# H_Connecties.net
KiCad netlist of a schematic drawn in Altium Designer
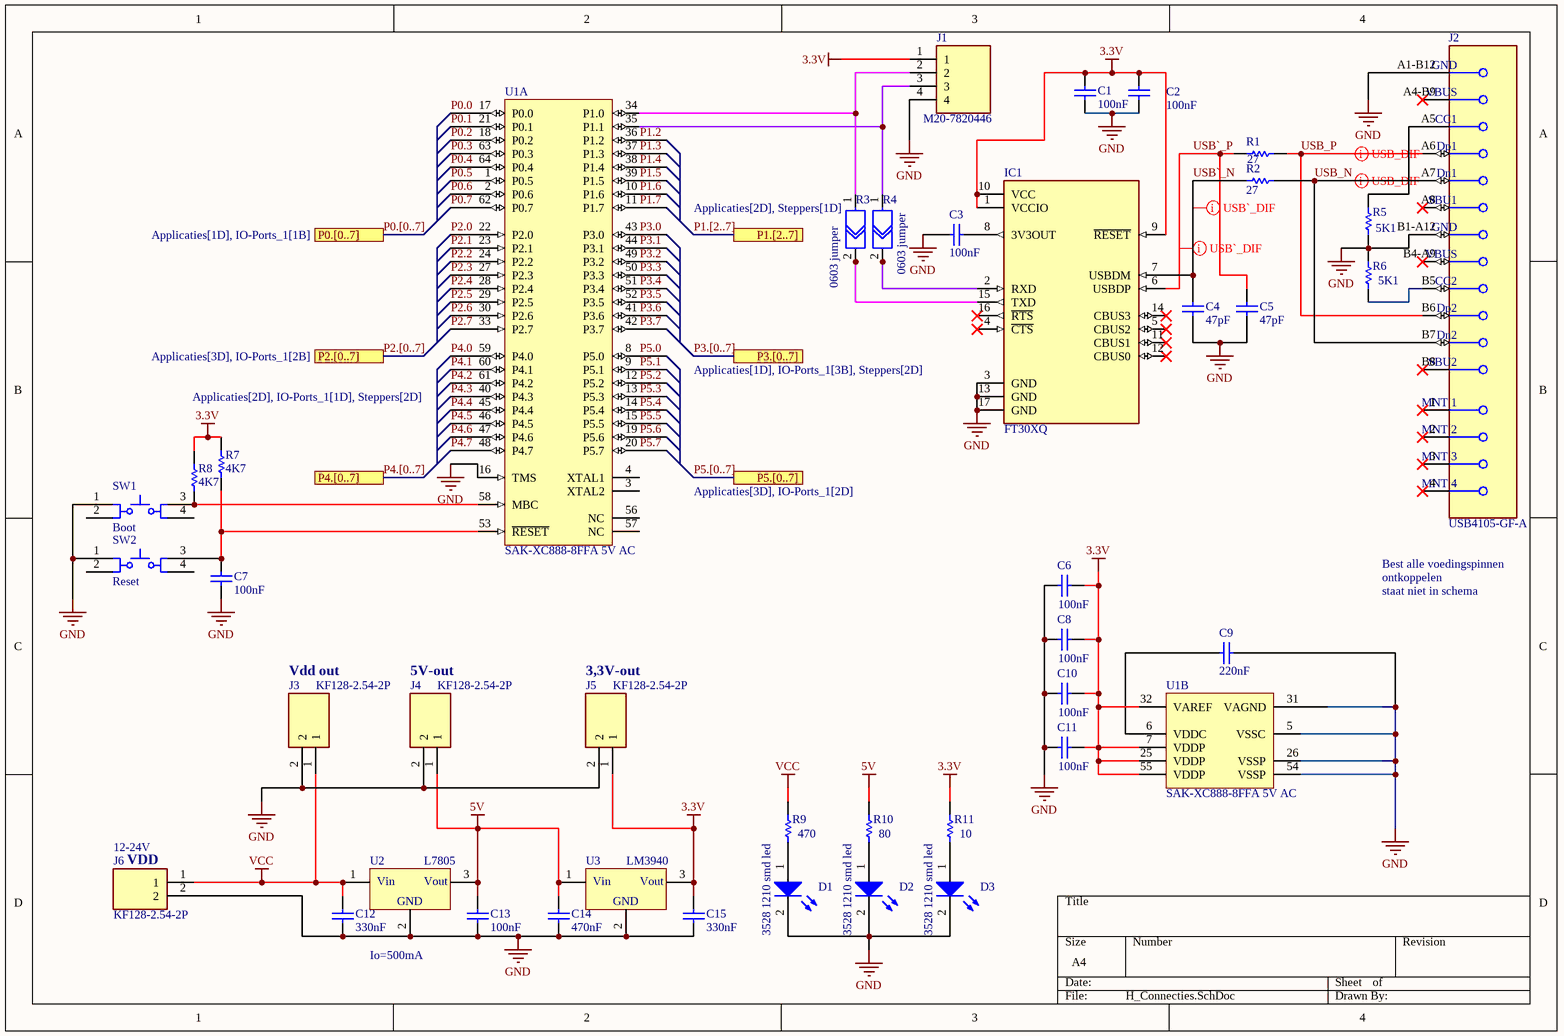
[diagram p0: H_Connecties.SchDoc]

(export (version "E")
  (design (tool "Eeschema 10.0.6"))
  (components
    (comp (ref "C1")
      (value "100nF")
      (footprint "CAPC1608X90X35LL15T15")
      (fields
        (field (name "MANUFACTURER") "AVX Interconnect / Elco")
        (field (name "PART NUMBER") "0603ZC101KAT2A")
      )
      (libsource (lib "Altium Content Vault") (part "CAP"))
    )
    (comp (ref "C2")
      (value "100nF")
      (footprint "CAPC1608X90X35LL15T15")
      (fields
        (field (name "MANUFACTURER") "AVX Interconnect / Elco")
        (field (name "PART NUMBER") "0603ZC101KAT2A")
      )
      (libsource (lib "Altium Content Vault") (part "CAP"))
    )
    (comp (ref "C3")
      (value "100nF")
      (footprint "CAPC1608X90X35LL15T15")
      (fields
        (field (name "MANUFACTURER") "AVX Interconnect / Elco")
        (field (name "PART NUMBER") "0603ZC101KAT2A")
      )
      (libsource (lib "Altium Content Vault") (part "CAP"))
    )
    (comp (ref "C4")
      (value "47pF")
      (footprint "CAPC1608X90X35LL15T15")
      (fields
        (field (name "MANUFACTURER") "AVX Interconnect / Elco")
        (field (name "PART NUMBER") "0603ZC101KAT2A")
      )
      (libsource (lib "Altium Content Vault") (part "CAP"))
    )
    (comp (ref "C5")
      (value "47pF")
      (footprint "CAPC1608X90X35LL15T15")
      (fields
        (field (name "MANUFACTURER") "AVX Interconnect / Elco")
        (field (name "PART NUMBER") "0603ZC101KAT2A")
      )
      (libsource (lib "Altium Content Vault") (part "CAP"))
    )
    (comp (ref "C6")
      (value "100nF")
      (footprint "CAPC1608X92X38NL15T08")
      (fields (field (name "MANUFACTURER") "Vitramon") (field (name "PART NUMBER") "VJ0603Y104KXJAP"))
      (libsource (lib "Altium Content Vault") (part "CAP"))
    )
    (comp (ref "C7")
      (value "100nF")
      (footprint "CAPC1608X90X35LL15T15")
      (fields
        (field (name "MANUFACTURER") "AVX Interconnect / Elco")
        (field (name "PART NUMBER") "0603ZC101KAT2A")
      )
      (libsource (lib "Altium Content Vault") (part "CAP"))
    )
    (comp (ref "C8")
      (value "100nF")
      (footprint "CAPC1608X92X38NL15T08")
      (fields (field (name "MANUFACTURER") "Vitramon") (field (name "PART NUMBER") "VJ0603Y104KXJAP"))
      (libsource (lib "Altium Content Vault") (part "CAP"))
    )
    (comp (ref "C9")
      (value "220nF")
      (footprint "CAPC1608X95X40LL15T15")
      (fields (field (name "PART NUMBER") "VJ0603Y224KXXCW1BC") (field (name "MANUFACTURER") "Vitramon"))
      (libsource (lib "Altium Content Vault") (part "CAP"))
    )
    (comp (ref "C10")
      (value "100nF")
      (footprint "CAPC1608X92X38NL15T08")
      (fields (field (name "MANUFACTURER") "Vitramon") (field (name "PART NUMBER") "VJ0603Y104KXJAP"))
      (libsource (lib "Altium Content Vault") (part "CAP"))
    )
    (comp (ref "C11")
      (value "100nF")
      (footprint "CAPC1608X92X38NL15T08")
      (fields (field (name "MANUFACTURER") "Vitramon") (field (name "PART NUMBER") "VJ0603Y104KXJAP"))
      (libsource (lib "Altium Content Vault") (part "CAP"))
    )
    (comp (ref "C12")
      (value "330nF")
      (footprint "CAPC1608X90X35LL15T15")
      (fields
        (field (name "MANUFACTURER") "AVX Interconnect / Elco")
        (field (name "PART NUMBER") "0603ZC101KAT2A")
      )
      (libsource (lib "Altium Content Vault") (part "CAP"))
    )
    (comp (ref "C13")
      (value "100nF")
      (footprint "CAPC1608X90X35LL15T15")
      (fields
        (field (name "MANUFACTURER") "AVX Interconnect / Elco")
        (field (name "PART NUMBER") "0603ZC101KAT2A")
      )
      (libsource (lib "Altium Content Vault") (part "CAP"))
    )
    (comp (ref "C14")
      (value "470nF")
      (footprint "CAPC1608X90X35LL15T15")
      (fields
        (field (name "MANUFACTURER") "AVX Interconnect / Elco")
        (field (name "PART NUMBER") "0603ZC101KAT2A")
      )
      (libsource (lib "Altium Content Vault") (part "CAP"))
    )
    (comp (ref "C15")
      (value "330nF")
      (footprint "CAPC1608X90X35LL15T15")
      (fields
        (field (name "MANUFACTURER") "AVX Interconnect / Elco")
        (field (name "PART NUMBER") "0603ZC101KAT2A")
      )
      (libsource (lib "Altium Content Vault") (part "CAP"))
    )
    (comp (ref "D1")
      (value "3528 1210 smd led")
      (footprint "WL-SITW_3528_L3.5W2.8H1.9")
      (description "15414185BA210 WL-SITW SMT InfraRed TopLED Waterclear")
      (libsource (lib "Altium Content Vault") (part "LED_Infrared_1A-2K"))
    )
    (comp (ref "D2")
      (value "3528 1210 smd led")
      (footprint "WL-SITW_3528_L3.5W2.8H1.9")
      (description "15414185BA210 WL-SITW SMT InfraRed TopLED Waterclear")
      (libsource (lib "Altium Content Vault") (part "LED_Infrared_1A-2K"))
    )
    (comp (ref "D3")
      (value "3528 1210 smd led")
      (footprint "WL-SITW_3528_L3.5W2.8H1.9")
      (description "15414185BA210 WL-SITW SMT InfraRed TopLED Waterclear")
      (libsource (lib "Altium Content Vault") (part "LED_Infrared_1A-2K"))
    )
    (comp (ref "IC1") (value "FT30XQ") (footprint "FT30XQ") (libsource (lib "Eigen_schemas") (part "FT30XQ")))
    (comp (ref "J1")
      (value "M20-7820446")
      (footprint "M20-4pin")
      (description "Connector")
      (fields (field (name "MOUSER PART NUMBER") "855-M20-7820446"))
      (libsource (lib "*") (part "M20-7820446"))
    )
    (comp (ref "J2")
      (value "USB4105-GF-A")
      (footprint "FP-USB4105-GF-A-MFG")
      (description "CONN RCPT USB2.0 TYPEC 5A")
      (fields
        (field (name "MANUFACTURER") "GCT")
        (field (name "OCTOPART") "https://octopart.com/usb4105-gf-a-gct-106627878")
      )
      (libsource (lib "Altium Content Vault") (part "e7c17a616881a82b79941196b4bec10"))
    )
    (comp (ref "J3")
      (value "KF128-2.54-2P")
      (footprint "KF128-2.54-2P")
      (description "Connector")
      (libsource (lib "*") (part "KF128-2.54-2P"))
    )
    (comp (ref "J4")
      (value "KF128-2.54-2P")
      (footprint "KF128-2.54-2P")
      (description "Connector")
      (libsource (lib "*") (part "KF128-2.54-2P"))
    )
    (comp (ref "J5")
      (value "KF128-2.54-2P")
      (footprint "KF128-2.54-2P")
      (description "Connector")
      (libsource (lib "*") (part "KF128-2.54-2P"))
    )
    (comp (ref "J6")
      (value "KF128-2.54-2P")
      (footprint "KF128-2.54-2P")
      (description "Connector")
      (libsource (lib "") (part "KF128-2.54-2P_1"))
    )
    (comp (ref "R1")
      (value "27")
      (footprint "RESC1608X55X25LL10T15")
      (fields (field (name "PART NUMBER") "RC0603FR-102KL") (field (name "MANUFACTURER") "Yageo"))
      (libsource (lib "Altium Content Vault") (part "RES"))
    )
    (comp (ref "R2")
      (value "27")
      (footprint "RESC1608X55X25LL10T15")
      (fields (field (name "PART NUMBER") "RC0603FR-102KL") (field (name "MANUFACTURER") "Yageo"))
      (libsource (lib "Altium Content Vault") (part "RES"))
    )
    (comp (ref "R3")
      (value "0603 jumper")
      (footprint "0603 jumper")
      (libsource (lib "Eigen_schemas") (part "0603 jumper"))
    )
    (comp (ref "R4")
      (value "0603 jumper")
      (footprint "0603 jumper")
      (libsource (lib "Eigen_schemas") (part "0603 jumper"))
    )
    (comp (ref "R5")
      (value "5K1")
      (footprint "RESC1608X55X25LL10T15")
      (fields (field (name "PART NUMBER") "RC0603FR-102KL") (field (name "MANUFACTURER") "Yageo"))
      (libsource (lib "Altium Content Vault") (part "RES"))
    )
    (comp (ref "R6")
      (value "5K1")
      (footprint "RESC1608X55X25LL10T15")
      (fields (field (name "PART NUMBER") "RC0603FR-102KL") (field (name "MANUFACTURER") "Yageo"))
      (libsource (lib "Altium Content Vault") (part "RES"))
    )
    (comp (ref "R7")
      (value "4K7")
      (footprint "RESC1608X55X25LL10T15")
      (fields (field (name "PART NUMBER") "RC0603FR-102KL") (field (name "MANUFACTURER") "Yageo"))
      (libsource (lib "Altium Content Vault") (part "RES"))
    )
    (comp (ref "R8")
      (value "4K7")
      (footprint "RESC1608X55X25LL10T15")
      (fields (field (name "PART NUMBER") "RC0603FR-102KL") (field (name "MANUFACTURER") "Yageo"))
      (libsource (lib "Altium Content Vault") (part "RES"))
    )
    (comp (ref "R9")
      (value "470")
      (footprint "RESC1608X55X25LL10T15")
      (fields (field (name "PART NUMBER") "RC0603FR-102KL") (field (name "MANUFACTURER") "Yageo"))
      (libsource (lib "Altium Content Vault") (part "RES"))
    )
    (comp (ref "R10")
      (value "80")
      (footprint "RESC1608X55X25LL10T15")
      (fields (field (name "PART NUMBER") "RC0603FR-102KL") (field (name "MANUFACTURER") "Yageo"))
      (libsource (lib "Altium Content Vault") (part "RES"))
    )
    (comp (ref "R11")
      (value "10")
      (footprint "RESC1608X55X25LL10T15")
      (fields (field (name "PART NUMBER") "RC0603FR-102KL") (field (name "MANUFACTURER") "Yageo"))
      (libsource (lib "Altium Content Vault") (part "RES"))
    )
    (comp (ref "SW1")
      (value "Boot")
      (footprint "ESWI-TL1105SPF_V")
      (description "Tact Switch, SPST-NO, 50 mA, 12 VDC, -20 to 70 degC, 4-Pin THD, RoHS, Bulk")
      (fields (field (name "MANUFACTURER") "E-Switch"))
      (libsource (lib "Altium Content Vault") (part "SW-SPST-NO-4"))
    )
    (comp (ref "SW2")
      (value "Reset")
      (footprint "ESWI-TL1105SPF_V")
      (description "Tact Switch, SPST-NO, 50 mA, 12 VDC, -20 to 70 degC, 4-Pin THD, RoHS, Bulk")
      (fields (field (name "MANUFACTURER") "E-Switch"))
      (libsource (lib "Altium Content Vault") (part "SW-SPST-NO-4"))
    )
    (comp (ref "U1")
      (value "SAK-XC888-8FFA 5V AC")
      (footprint "INF-PG-TQFP-64-8_L")
      (fields (field (name "MANUFACTURER") "Infineon"))
      (libsource (lib "Altium Content Vault") (part "INF-SAx-XC888x-PG-LQFP-64"))
    )
    (comp (ref "U2")
      (value "L7805")
      (footprint "DPAK")
      (description "Linaire spannings omvormer")
      (libsource (lib "Eigen_schemas") (part "L7805"))
    )
    (comp (ref "U3")
      (value "LM3940")
      (footprint "SOT-233")
      (description "5V --> 3.3V")
      (libsource (lib "Eigen_schemas") (part "LM3940"))
    )
  )
  (nets
    (net (code "1") (name "/P0.0") (class "Default")
      (node (ref "U1") (pin "17") (pinfunction "P0.0_17") (pintype "bidirectional"))
    )
    (net (code "2") (name "/P0.1") (class "Default")
      (node (ref "U1") (pin "21") (pinfunction "P0.1_21") (pintype "bidirectional"))
    )
    (net (code "3") (name "/P0.2") (class "Default")
      (node (ref "U1") (pin "18") (pinfunction "P0.2_18") (pintype "bidirectional"))
    )
    (net (code "4") (name "/P0.3") (class "Default")
      (node (ref "U1") (pin "63") (pinfunction "P0.3_63") (pintype "bidirectional"))
    )
    (net (code "5") (name "/P0.4") (class "Default")
      (node (ref "U1") (pin "64") (pinfunction "P0.4_64") (pintype "bidirectional"))
    )
    (net (code "6") (name "/P0.5") (class "Default")
      (node (ref "U1") (pin "1") (pinfunction "P0.5_1") (pintype "bidirectional"))
    )
    (net (code "7") (name "/P0.6") (class "Default")
      (node (ref "U1") (pin "2") (pinfunction "P0.6_2") (pintype "bidirectional"))
    )
    (net (code "8") (name "/P0.7") (class "Default")
      (node (ref "U1") (pin "62") (pinfunction "P0.7_62") (pintype "bidirectional"))
    )
    (net (code "10") (name "/P1.2") (class "Default")
      (node (ref "U1") (pin "36") (pinfunction "P1.2_36") (pintype "bidirectional"))
    )
    (net (code "11") (name "/P1.3") (class "Default")
      (node (ref "U1") (pin "37") (pinfunction "P1.3_37") (pintype "bidirectional"))
    )
    (net (code "12") (name "/P1.4") (class "Default")
      (node (ref "U1") (pin "38") (pinfunction "P1.4_38") (pintype "bidirectional"))
    )
    (net (code "13") (name "/P1.5") (class "Default")
      (node (ref "U1") (pin "39") (pinfunction "P1.5_39") (pintype "bidirectional"))
    )
    (net (code "14") (name "/P1.6") (class "Default")
      (node (ref "U1") (pin "10") (pinfunction "P1.6_10") (pintype "bidirectional"))
    )
    (net (code "15") (name "/P1.7") (class "Default")
      (node (ref "U1") (pin "11") (pinfunction "P1.7_11") (pintype "bidirectional"))
    )
    (net (code "17") (name "/P2.0") (class "Default")
      (node (ref "U1") (pin "22") (pinfunction "P2.0_22") (pintype "input"))
    )
    (net (code "18") (name "/P2.1") (class "Default")
      (node (ref "U1") (pin "23") (pinfunction "P2.1_23") (pintype "input"))
    )
    (net (code "19") (name "/P2.2") (class "Default")
      (node (ref "U1") (pin "24") (pinfunction "P2.2_24") (pintype "input"))
    )
    (net (code "20") (name "/P2.3") (class "Default")
      (node (ref "U1") (pin "27") (pinfunction "P2.3_27") (pintype "input"))
    )
    (net (code "21") (name "/P2.4") (class "Default")
      (node (ref "U1") (pin "28") (pinfunction "P2.4_28") (pintype "input"))
    )
    (net (code "22") (name "/P2.5") (class "Default")
      (node (ref "U1") (pin "29") (pinfunction "P2.5_29") (pintype "input"))
    )
    (net (code "23") (name "/P2.6") (class "Default")
      (node (ref "U1") (pin "30") (pinfunction "P2.6_30") (pintype "input"))
    )
    (net (code "24") (name "/P2.7") (class "Default")
      (node (ref "U1") (pin "33") (pinfunction "P2.7_33") (pintype "input"))
    )
    (net (code "26") (name "/P3.0") (class "Default")
      (node (ref "U1") (pin "43") (pinfunction "P3.0_43") (pintype "bidirectional"))
    )
    (net (code "27") (name "/P3.1") (class "Default")
      (node (ref "U1") (pin "44") (pinfunction "P3.1_44") (pintype "bidirectional"))
    )
    (net (code "28") (name "/P3.2") (class "Default")
      (node (ref "U1") (pin "49") (pinfunction "P3.2_49") (pintype "bidirectional"))
    )
    (net (code "29") (name "/P3.3") (class "Default")
      (node (ref "U1") (pin "50") (pinfunction "P3.3_50") (pintype "bidirectional"))
    )
    (net (code "30") (name "/P3.4") (class "Default")
      (node (ref "U1") (pin "51") (pinfunction "P3.4_51") (pintype "bidirectional"))
    )
    (net (code "31") (name "/P3.5") (class "Default")
      (node (ref "U1") (pin "52") (pinfunction "P3.5_52") (pintype "bidirectional"))
    )
    (net (code "32") (name "/P3.6") (class "Default")
      (node (ref "U1") (pin "41") (pinfunction "P3.6_41") (pintype "bidirectional"))
    )
    (net (code "33") (name "/P3.7") (class "Default")
      (node (ref "U1") (pin "42") (pinfunction "P3.7_42") (pintype "bidirectional"))
    )
    (net (code "35") (name "/P4.0") (class "Default")
      (node (ref "U1") (pin "59") (pinfunction "P4.0_59") (pintype "bidirectional"))
    )
    (net (code "36") (name "/P4.1") (class "Default")
      (node (ref "U1") (pin "60") (pinfunction "P4.1_60") (pintype "bidirectional"))
    )
    (net (code "37") (name "/P4.2") (class "Default")
      (node (ref "U1") (pin "61") (pinfunction "P4.2_61") (pintype "bidirectional"))
    )
    (net (code "38") (name "/P4.3") (class "Default")
      (node (ref "U1") (pin "40") (pinfunction "P4.3_40") (pintype "bidirectional"))
    )
    (net (code "39") (name "/P4.4") (class "Default")
      (node (ref "U1") (pin "45") (pinfunction "P4.4_45") (pintype "bidirectional"))
    )
    (net (code "40") (name "/P4.5") (class "Default")
      (node (ref "U1") (pin "46") (pinfunction "P4.5_46") (pintype "bidirectional"))
    )
    (net (code "41") (name "/P4.6") (class "Default")
      (node (ref "U1") (pin "47") (pinfunction "P4.6_47") (pintype "bidirectional"))
    )
    (net (code "42") (name "/P4.7") (class "Default")
      (node (ref "U1") (pin "48") (pinfunction "P4.7_48") (pintype "bidirectional"))
    )
    (net (code "44") (name "/P5.0") (class "Default")
      (node (ref "U1") (pin "8") (pinfunction "P5.0_8") (pintype "bidirectional"))
    )
    (net (code "45") (name "/P5.1") (class "Default")
      (node (ref "U1") (pin "9") (pinfunction "P5.1_9") (pintype "bidirectional"))
    )
    (net (code "46") (name "/P5.2") (class "Default")
      (node (ref "U1") (pin "12") (pinfunction "P5.2_12") (pintype "bidirectional"))
    )
    (net (code "47") (name "/P5.3") (class "Default")
      (node (ref "U1") (pin "13") (pinfunction "P5.3_13") (pintype "bidirectional"))
    )
    (net (code "48") (name "/P5.4") (class "Default")
      (node (ref "U1") (pin "14") (pinfunction "P5.4_14") (pintype "bidirectional"))
    )
    (net (code "49") (name "/P5.5") (class "Default")
      (node (ref "U1") (pin "15") (pinfunction "P5.5_15") (pintype "bidirectional"))
    )
    (net (code "50") (name "/P5.6") (class "Default")
      (node (ref "U1") (pin "19") (pinfunction "P5.6_19") (pintype "bidirectional"))
    )
    (net (code "51") (name "/P5.7") (class "Default")
      (node (ref "U1") (pin "20") (pinfunction "P5.7_20") (pintype "bidirectional"))
    )
    (net (code "53") (name "/USB_N") (class "Default")
      (node (ref "J2") (pin "A7") (pinfunction "Dn1_A7") (pintype "bidirectional"))
      (node (ref "J2") (pin "B7") (pinfunction "Dn2_B7") (pintype "bidirectional"))
      (node (ref "R2") (pin "1") (pinfunction "1_1") (pintype "passive"))
    )
    (net (code "54") (name "/USB_P") (class "Default")
      (node (ref "J2") (pin "A6") (pinfunction "Dp1_A6") (pintype "bidirectional"))
      (node (ref "J2") (pin "B6") (pinfunction "Dp2_B6") (pintype "bidirectional"))
      (node (ref "R1") (pin "1") (pinfunction "1_1") (pintype "passive"))
    )
    (net (code "55") (name "/USB`_N") (class "Default")
      (node (ref "C4") (pin "2") (pinfunction "2_2") (pintype "passive"))
      (node (ref "IC1") (pin "7") (pinfunction "USBDM_7") (pintype "input"))
      (node (ref "R2") (pin "2") (pinfunction "2_2") (pintype "passive"))
    )
    (net (code "56") (name "/USB`_P") (class "Default")
      (node (ref "C5") (pin "2") (pinfunction "2_2") (pintype "passive"))
      (node (ref "IC1") (pin "6") (pinfunction "USBDP_6") (pintype "input"))
      (node (ref "R1") (pin "2") (pinfunction "2_2") (pintype "passive"))
    )
    (net (code "57") (name "3.3V") (class "Default")
      (node (ref "C1") (pin "2") (pinfunction "2_2") (pintype "passive"))
      (node (ref "C10") (pin "2") (pinfunction "2_2") (pintype "passive"))
      (node (ref "C11") (pin "2") (pinfunction "2_2") (pintype "passive"))
      (node (ref "C15") (pin "2") (pinfunction "2_2") (pintype "passive"))
      (node (ref "C2") (pin "2") (pinfunction "2_2") (pintype "passive"))
      (node (ref "C6") (pin "2") (pinfunction "2_2") (pintype "passive"))
      (node (ref "C8") (pin "2") (pinfunction "2_2") (pintype "passive"))
      (node (ref "IC1") (pin "1") (pinfunction "VCCIO_1") (pintype "power_in"))
      (node (ref "IC1") (pin "10") (pinfunction "VCC_10") (pintype "power_in"))
      (node (ref "IC1") (pin "9") (pinfunction "~{RESET}_9") (pintype "input"))
      (node (ref "J1") (pin "1") (pinfunction "1_1") (pintype "passive"))
      (node (ref "J5") (pin "1") (pinfunction "1_1") (pintype "passive"))
      (node (ref "R11") (pin "1") (pinfunction "1_1") (pintype "passive"))
      (node (ref "R7") (pin "2") (pinfunction "2_2") (pintype "passive"))
      (node (ref "R8") (pin "2") (pinfunction "2_2") (pintype "passive"))
      (node (ref "U1") (pin "25") (pinfunction "VDDP_25") (pintype "power_in"))
      (node (ref "U1") (pin "32") (pinfunction "VAREF_32") (pintype "power_in"))
      (node (ref "U1") (pin "55") (pinfunction "VDDP_55") (pintype "power_in"))
      (node (ref "U1") (pin "7") (pinfunction "VDDP_7") (pintype "power_in"))
      (node (ref "U3") (pin "3") (pinfunction "3_3") (pintype "passive"))
    )
    (net (code "58") (name "5V") (class "Default")
      (node (ref "C13") (pin "2") (pinfunction "2_2") (pintype "passive"))
      (node (ref "C14") (pin "2") (pinfunction "2_2") (pintype "passive"))
      (node (ref "J4") (pin "1") (pinfunction "1_1") (pintype "passive"))
      (node (ref "R10") (pin "1") (pinfunction "1_1") (pintype "passive"))
      (node (ref "U2") (pin "3") (pinfunction "3_3") (pintype "passive"))
      (node (ref "U3") (pin "1") (pintype "passive"))
    )
    (net (code "59") (name "GND") (class "Default")
      (node (ref "C1") (pin "1") (pinfunction "1_1") (pintype "passive"))
      (node (ref "C10") (pin "1") (pinfunction "1_1") (pintype "passive"))
      (node (ref "C11") (pin "1") (pinfunction "1_1") (pintype "passive"))
      (node (ref "C12") (pin "1") (pinfunction "1_1") (pintype "passive"))
      (node (ref "C13") (pin "1") (pinfunction "1_1") (pintype "passive"))
      (node (ref "C14") (pin "1") (pinfunction "1_1") (pintype "passive"))
      (node (ref "C15") (pin "1") (pinfunction "1_1") (pintype "passive"))
      (node (ref "C2") (pin "1") (pinfunction "1_1") (pintype "passive"))
      (node (ref "C3") (pin "2") (pinfunction "2_2") (pintype "passive"))
      (node (ref "C4") (pin "1") (pinfunction "1_1") (pintype "passive"))
      (node (ref "C5") (pin "1") (pinfunction "1_1") (pintype "passive"))
      (node (ref "C6") (pin "1") (pinfunction "1_1") (pintype "passive"))
      (node (ref "C7") (pin "1") (pinfunction "1_1") (pintype "passive"))
      (node (ref "C8") (pin "1") (pinfunction "1_1") (pintype "passive"))
      (node (ref "C9") (pin "2") (pinfunction "2_2") (pintype "passive"))
      (node (ref "D1") (pin "2") (pinfunction "K_2") (pintype "passive"))
      (node (ref "D2") (pin "2") (pinfunction "K_2") (pintype "passive"))
      (node (ref "D3") (pin "2") (pinfunction "K_2") (pintype "passive"))
      (node (ref "IC1") (pin "13") (pinfunction "GND_13") (pintype "power_in"))
      (node (ref "IC1") (pin "17") (pinfunction "GND_17") (pintype "power_in"))
      (node (ref "IC1") (pin "3") (pinfunction "GND_3") (pintype "power_in"))
      (node (ref "J1") (pin "4") (pinfunction "4_4") (pintype "passive"))
      (node (ref "J2") (pin "A1-B12") (pinfunction "GND_A1-B12") (pintype "power_in"))
      (node (ref "J2") (pin "B1-A12") (pinfunction "GND_B1-A12") (pintype "bidirectional"))
      (node (ref "J3") (pin "2") (pinfunction "2_2") (pintype "passive"))
      (node (ref "J4") (pin "2") (pinfunction "2_2") (pintype "passive"))
      (node (ref "J5") (pin "2") (pinfunction "2_2") (pintype "passive"))
      (node (ref "J6") (pin "2") (pinfunction "2_2") (pintype "passive"))
      (node (ref "R5") (pin "2") (pinfunction "2_2") (pintype "passive"))
      (node (ref "R6") (pin "1") (pinfunction "1_1") (pintype "passive"))
      (node (ref "SW1") (pin "1") (pinfunction "1_1") (pintype "passive"))
      (node (ref "SW2") (pin "1") (pinfunction "1_1") (pintype "passive"))
      (node (ref "U1") (pin "16") (pinfunction "TMS_16") (pintype "input"))
      (node (ref "U1") (pin "26") (pinfunction "VSSP_26") (pintype "power_in"))
      (node (ref "U1") (pin "31") (pinfunction "VAGND_31") (pintype "power_in"))
      (node (ref "U1") (pin "5") (pinfunction "VSSC_5") (pintype "power_in"))
      (node (ref "U1") (pin "54") (pinfunction "VSSP_54") (pintype "power_in"))
      (node (ref "U2") (pin "2") (pinfunction "2_2") (pintype "passive"))
      (node (ref "U3") (pin "2") (pinfunction "2_2") (pintype "passive"))
    )
    (net (code "60") (name "Net-(D1-A)") (class "Default")
      (node (ref "D1") (pin "1") (pinfunction "A_1") (pintype "passive"))
      (node (ref "R9") (pin "2") (pinfunction "2_2") (pintype "passive"))
    )
    (net (code "61") (name "Net-(D2-A)") (class "Default")
      (node (ref "D2") (pin "1") (pinfunction "A_1") (pintype "passive"))
      (node (ref "R10") (pin "2") (pinfunction "2_2") (pintype "passive"))
    )
    (net (code "62") (name "Net-(D3-A)") (class "Default")
      (node (ref "D3") (pin "1") (pinfunction "A_1") (pintype "passive"))
      (node (ref "R11") (pin "2") (pinfunction "2_2") (pintype "passive"))
    )
    (net (code "63") (name "Net-(IC1-3V3OUT)") (class "Default")
      (node (ref "C3") (pin "1") (pinfunction "1_1") (pintype "passive"))
      (node (ref "IC1") (pin "8") (pinfunction "3V3OUT_8") (pintype "output"))
    )
    (net (code "64") (name "Net-(IC1-RXD)") (class "Default")
      (node (ref "IC1") (pin "2") (pinfunction "RXD_2") (pintype "input"))
      (node (ref "R4") (pin "2") (pinfunction "2_2") (pintype "passive"))
    )
    (net (code "65") (name "Net-(IC1-TXD)") (class "Default")
      (node (ref "IC1") (pin "15") (pinfunction "TXD_15") (pintype "output"))
      (node (ref "R3") (pin "2") (pinfunction "2_2") (pintype "passive"))
    )
    (net (code "66") (name "Net-(J2-CC1)") (class "Default")
      (node (ref "J2") (pin "A5") (pinfunction "CC1_A5") (pintype "power_in"))
      (node (ref "R5") (pin "1") (pinfunction "1_1") (pintype "passive"))
    )
    (net (code "67") (name "Net-(J2-CC2)") (class "Default")
      (node (ref "J2") (pin "B5") (pinfunction "CC2_B5") (pintype "bidirectional"))
      (node (ref "R6") (pin "2") (pinfunction "2_2") (pintype "passive"))
    )
    (net (code "68") (name "Net-(U1A-MBC)") (class "Default")
      (node (ref "R8") (pin "1") (pinfunction "1_1") (pintype "passive"))
      (node (ref "SW1") (pin "3") (pinfunction "3_3") (pintype "passive"))
      (node (ref "U1") (pin "58") (pinfunction "MBC_58") (pintype "input"))
    )
    (net (code "69") (name "Net-(U1A-P1.0)") (class "Default")
      (node (ref "J1") (pin "2") (pinfunction "2_2") (pintype "passive"))
      (node (ref "R3") (pin "1") (pinfunction "1_1") (pintype "passive"))
      (node (ref "U1") (pin "34") (pinfunction "P1.0_34") (pintype "bidirectional"))
    )
    (net (code "70") (name "Net-(U1A-P1.1)") (class "Default")
      (node (ref "J1") (pin "3") (pinfunction "3_3") (pintype "passive"))
      (node (ref "R4") (pin "1") (pinfunction "1_1") (pintype "passive"))
      (node (ref "U1") (pin "35") (pinfunction "P1.1_35") (pintype "bidirectional"))
    )
    (net (code "71") (name "Net-(U1A-~{RESET})") (class "Default")
      (node (ref "C7") (pin "2") (pinfunction "2_2") (pintype "passive"))
      (node (ref "R7") (pin "1") (pinfunction "1_1") (pintype "passive"))
      (node (ref "SW2") (pin "3") (pinfunction "3_3") (pintype "passive"))
      (node (ref "U1") (pin "53") (pinfunction "~{RESET}_53") (pintype "input"))
    )
    (net (code "72") (name "Net-(U1B-VDDC)") (class "Default")
      (node (ref "C9") (pin "1") (pinfunction "1_1") (pintype "passive"))
      (node (ref "U1") (pin "6") (pinfunction "VDDC_6") (pintype "power_in"))
    )
    (net (code "73") (name "VCC") (class "Default")
      (node (ref "C12") (pin "2") (pinfunction "2_2") (pintype "passive"))
      (node (ref "J3") (pin "1") (pinfunction "1_1") (pintype "passive"))
      (node (ref "J6") (pin "1") (pinfunction "1_1") (pintype "passive"))
      (node (ref "R9") (pin "1") (pinfunction "1_1") (pintype "passive"))
      (node (ref "U2") (pin "1") (pintype "passive"))
    )
    (net (code "74") (name "unconnected-(IC1-CBUS0-Pad12)") (class "Default")
      (node (ref "IC1") (pin "12") (pinfunction "CBUS0_12") (pintype "bidirectional+no_connect"))
    )
    (net (code "75") (name "unconnected-(IC1-CBUS1-Pad11)") (class "Default")
      (node (ref "IC1") (pin "11") (pinfunction "CBUS1_11") (pintype "bidirectional+no_connect"))
    )
    (net (code "76") (name "unconnected-(IC1-CBUS2-Pad5)") (class "Default")
      (node (ref "IC1") (pin "5") (pinfunction "CBUS2_5") (pintype "bidirectional+no_connect"))
    )
    (net (code "77") (name "unconnected-(IC1-CBUS3-Pad14)") (class "Default")
      (node (ref "IC1") (pin "14") (pinfunction "CBUS3_14") (pintype "bidirectional+no_connect"))
    )
    (net (code "78") (name "unconnected-(IC1-~{CTS}-Pad4)") (class "Default")
      (node (ref "IC1") (pin "4") (pinfunction "~{CTS}_4") (pintype "input+no_connect"))
    )
    (net (code "79") (name "unconnected-(IC1-~{RTS}-Pad16)") (class "Default")
      (node (ref "IC1") (pin "16") (pinfunction "~{RTS}_16") (pintype "output+no_connect"))
    )
    (net (code "80") (name "unconnected-(J2-MNT_1-Pad1)") (class "Default")
      (node (ref "J2") (pin "1") (pinfunction "MNT_1_1") (pintype "power_in+no_connect"))
    )
    (net (code "81") (name "unconnected-(J2-MNT_2-Pad2)") (class "Default")
      (node (ref "J2") (pin "2") (pinfunction "MNT_2_2") (pintype "power_in+no_connect"))
    )
    (net (code "82") (name "unconnected-(J2-MNT_3-Pad3)") (class "Default")
      (node (ref "J2") (pin "3") (pinfunction "MNT_3_3") (pintype "power_in+no_connect"))
    )
    (net (code "83") (name "unconnected-(J2-MNT_4-Pad4)") (class "Default")
      (node (ref "J2") (pin "4") (pinfunction "MNT_4_4") (pintype "power_in+no_connect"))
    )
    (net (code "84") (name "unconnected-(J2-SBU1-PadA8)") (class "Default")
      (node (ref "J2") (pin "A8") (pinfunction "SBU1_A8") (pintype "bidirectional+no_connect"))
    )
    (net (code "85") (name "unconnected-(J2-SBU2-PadB8)") (class "Default")
      (node (ref "J2") (pin "B8") (pinfunction "SBU2_B8") (pintype "power_in+no_connect"))
    )
    (net (code "86") (name "unconnected-(J2-VBUS-PadA4-B9)") (class "Default")
      (node (ref "J2") (pin "A4-B9") (pinfunction "VBUS_A4-B9") (pintype "power_in+no_connect"))
    )
    (net (code "87") (name "unconnected-(J2-VBUS-PadB4-A9)") (class "Default")
      (node (ref "J2") (pin "B4-A9") (pinfunction "VBUS_B4-A9") (pintype "bidirectional+no_connect"))
    )
    (net (code "88") (name "unconnected-(SW1-Pad2)") (class "Default")
      (node (ref "SW1") (pin "2") (pinfunction "2_2") (pintype "passive"))
    )
    (net (code "89") (name "unconnected-(SW1-Pad4)") (class "Default")
      (node (ref "SW1") (pin "4") (pinfunction "4_4") (pintype "passive"))
    )
    (net (code "90") (name "unconnected-(SW2-Pad2)") (class "Default")
      (node (ref "SW2") (pin "2") (pinfunction "2_2") (pintype "passive"))
    )
    (net (code "91") (name "unconnected-(SW2-Pad4)") (class "Default")
      (node (ref "SW2") (pin "4") (pinfunction "4_4") (pintype "passive"))
    )
    (net (code "92") (name "unconnected-(U1A-NC-Pad56)") (class "Default")
      (node (ref "U1") (pin "56") (pinfunction "NC_56") (pintype "passive"))
    )
    (net (code "93") (name "unconnected-(U1A-NC-Pad57)") (class "Default")
      (node (ref "U1") (pin "57") (pinfunction "NC_57") (pintype "passive"))
    )
    (net (code "94") (name "unconnected-(U1A-XTAL1-Pad4)") (class "Default")
      (node (ref "U1") (pin "4") (pinfunction "XTAL1_4") (pintype "passive"))
    )
    (net (code "95") (name "unconnected-(U1A-XTAL2-Pad3)") (class "Default")
      (node (ref "U1") (pin "3") (pinfunction "XTAL2_3") (pintype "passive"))
    )
  )
)
